# Sheet1_Cpu.net
KiCad netlist of a schematic drawn in Altium Designer
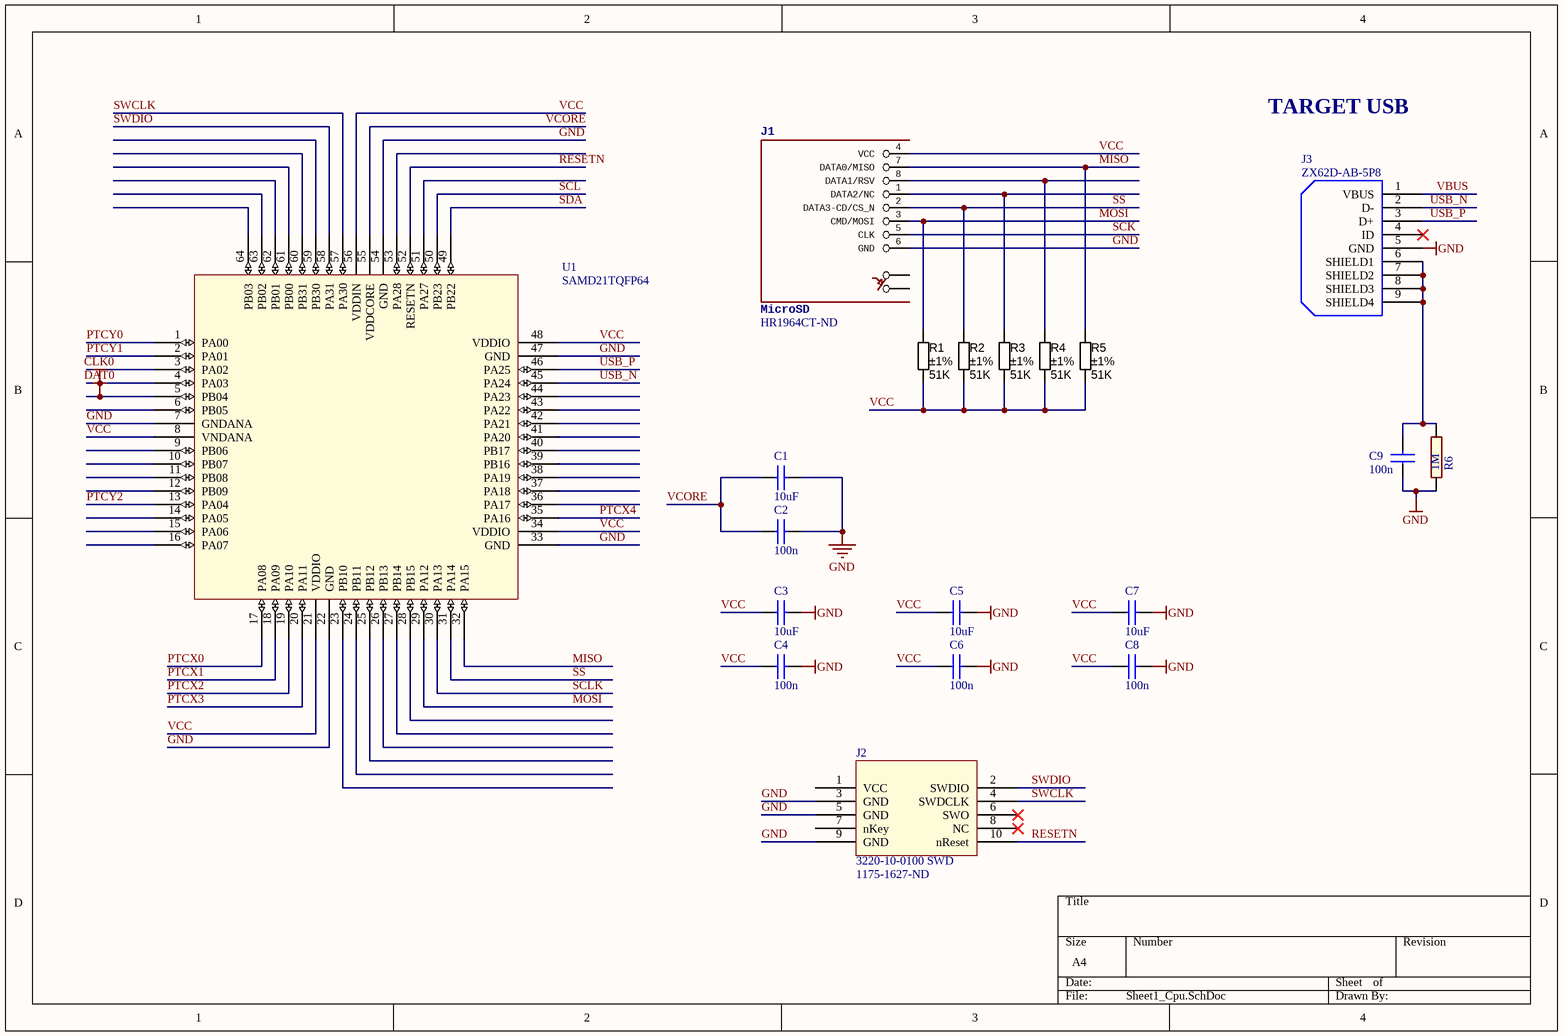
[diagram p0: Sheet1_Cpu.SchDoc]

(export (version "E")
  (design (tool "Eeschema 10.0.6"))
  (components
    (comp (ref "C1")
      (value "10uF")
      (footprint "AP1-00041")
      (description "Ceramic capacitor, SMD 0805, X5R, 10V, 10 %, (de19441)")
      (fields (field (name "TOLERANCE") "10%") (field (name "MANUFACTURER") "Murata"))
      (libsource (lib "AltiumDbLib") (part "CAP-NONPOL"))
    )
    (comp (ref "C2")
      (value "100n")
      (footprint "AP1-00001")
      (description "Ceramic capacitor, SMD 0402, X7R, 16V, +/-10%")
      (fields (field (name "TOLERANCE") "16V, +/-10%") (field (name "MANUFACTURER") "Kemet"))
      (libsource (lib "AltiumDbLib") (part "CAP-NONPOL"))
    )
    (comp (ref "C3")
      (value "10uF")
      (footprint "AP1-00041")
      (description "Ceramic capacitor, SMD 0805, X5R, 10V, 10 %, (de19441)")
      (fields (field (name "TOLERANCE") "10%") (field (name "MANUFACTURER") "Murata"))
      (libsource (lib "AltiumDbLib") (part "CAP-NONPOL"))
    )
    (comp (ref "C4")
      (value "100n")
      (footprint "AP1-00001")
      (description "Ceramic capacitor, SMD 0402, X7R, 16V, +/-10%")
      (fields (field (name "TOLERANCE") "16V, +/-10%") (field (name "MANUFACTURER") "Kemet"))
      (libsource (lib "AltiumDbLib") (part "CAP-NONPOL"))
    )
    (comp (ref "C5")
      (value "10uF")
      (footprint "AP1-00041")
      (description "Ceramic capacitor, SMD 0805, X5R, 10V, 10 %, (de19441)")
      (fields (field (name "TOLERANCE") "10%") (field (name "MANUFACTURER") "Murata"))
      (libsource (lib "AltiumDbLib") (part "CAP-NONPOL"))
    )
    (comp (ref "C6")
      (value "100n")
      (footprint "AP1-00001")
      (description "Ceramic capacitor, SMD 0402, X7R, 16V, +/-10%")
      (fields (field (name "TOLERANCE") "16V, +/-10%") (field (name "MANUFACTURER") "Kemet"))
      (libsource (lib "AltiumDbLib") (part "CAP-NONPOL"))
    )
    (comp (ref "C7")
      (value "10uF")
      (footprint "AP1-00041")
      (description "Ceramic capacitor, SMD 0805, X5R, 10V, 10 %, (de19441)")
      (fields (field (name "TOLERANCE") "10%") (field (name "MANUFACTURER") "Murata"))
      (libsource (lib "AltiumDbLib") (part "CAP-NONPOL"))
    )
    (comp (ref "C8")
      (value "100n")
      (footprint "AP1-00001")
      (description "Ceramic capacitor, SMD 0402, X7R, 16V, +/-10%")
      (fields (field (name "TOLERANCE") "16V, +/-10%") (field (name "MANUFACTURER") "Kemet"))
      (libsource (lib "AltiumDbLib") (part "CAP-NONPOL"))
    )
    (comp (ref "C9")
      (value "100n")
      (footprint "AP1-00001")
      (description "Ceramic capacitor, SMD 0402, X7R, 16V, +/-10%")
      (fields (field (name "TOLERANCE") "16V, +/-10%") (field (name "MANUFACTURER") "Kemet"))
      (libsource (lib "AltiumDbLib") (part "CAP-NONPOL"))
    )
    (comp (ref "J1")
      (value "MicroSD")
      (footprint "DM3AT-SF-PEJM5")
      (description "Hirose Electric Micro SD - DM3AT-SF-PEJM5")
      (fields (field (name "SUPPLIER PART NUMBER 1") "HR1964CT-ND"))
      (libsource (lib "DM3AT-SF-PEJM5") (part "DM3AT-SF-PEJM5"))
    )
    (comp (ref "J2")
      (value "3220-10-0100 SWD")
      (footprint "3220-10-0100")
      (description "HiRose 3220-10-0100 BOX HEADER, 0.050 10 POS")
      (fields (field (name "SUPPLIER PART NUMBER 1") "1175-1627-ND"))
      (libsource (lib "fastcar") (part "3220-10-0100-00"))
    )
    (comp (ref "J3")
      (value "ZX62D-AB-5P8")
      (footprint "AP8-00852")
      (description "Hirose ZX62D-AB-5P8 Micro USB AB Connector, Standard SMT + DIP")
      (libsource (lib "AltiumDbLib") (part "USB_AB"))
    )
    (comp (ref "R1")
      (value "51K")
      (footprint "RESC2012X70N")
      (description "Resistor SMD chip 51k Ohm 0.125W 1% 0805")
      (fields (field (name "TOLERANCE") "±1%") (field (name "Comment") "Thick Film"))
      (libsource (lib "") (part "RES_51K_0805_1%_1"))
    )
    (comp (ref "R2")
      (value "51K")
      (footprint "RESC2012X70N")
      (description "Resistor SMD chip 51k Ohm 0.125W 1% 0805")
      (fields (field (name "TOLERANCE") "±1%") (field (name "Comment") "Thick Film"))
      (libsource (lib "") (part "RES_51K_0805_1%_1"))
    )
    (comp (ref "R3")
      (value "51K")
      (footprint "RESC2012X70N")
      (description "Resistor SMD chip 51k Ohm 0.125W 1% 0805")
      (fields (field (name "TOLERANCE") "±1%") (field (name "Comment") "Thick Film"))
      (libsource (lib "PBL - Resistors") (part "RES_51K_0805_1%"))
    )
    (comp (ref "R4")
      (value "51K")
      (footprint "RESC2012X70N")
      (description "Resistor SMD chip 51k Ohm 0.125W 1% 0805")
      (fields (field (name "TOLERANCE") "±1%") (field (name "Comment") "Thick Film"))
      (libsource (lib "PBL - Resistors") (part "RES_51K_0805_1%"))
    )
    (comp (ref "R5")
      (value "51K")
      (footprint "RESC2012X70N")
      (description "Resistor SMD chip 51k Ohm 0.125W 1% 0805")
      (fields (field (name "TOLERANCE") "±1%") (field (name "Comment") "Thick Film"))
      (libsource (lib "PBL - Resistors") (part "RES_51K_0805_1%"))
    )
    (comp (ref "R6")
      (value "1M")
      (footprint "AP2-00011")
      (description "Thick film resistor, SMD 0402, 1/16W, 1%")
      (fields (field (name "TOLERANCE") "1 %") (field (name "MANUFACTURER") "KOA"))
      (libsource (lib "AltiumDbLib") (part "R2"))
    )
    (comp (ref "U1")
      (value "SAMD21TQFP64")
      (footprint "TSQFP50P1300X1300X120-64N")
      (libsource (lib "fastcar") (part "SAMD21TQFP64"))
    )
  )
  (nets
    (net (code "1") (name "/MISO") (class "Default")
      (node (ref "J1") (pin "7") (pinfunction "DATA0/MISO_7") (pintype "passive"))
      (node (ref "R5") (pin "1") (pinfunction "1_1") (pintype "passive"))
      (node (ref "U1") (pin "32") (pinfunction "PA15_32") (pintype "bidirectional"))
    )
    (net (code "2") (name "/MOSI") (class "Default")
      (node (ref "J1") (pin "3") (pinfunction "CMD/MOSI_3") (pintype "passive"))
      (node (ref "R1") (pin "2") (pinfunction "2_2") (pintype "passive"))
      (node (ref "U1") (pin "29") (pinfunction "PA12_29") (pintype "bidirectional"))
    )
    (net (code "3") (name "/PTCX0") (class "Default")
      (node (ref "U1") (pin "17") (pinfunction "PA08_17") (pintype "bidirectional"))
    )
    (net (code "4") (name "/PTCX1") (class "Default")
      (node (ref "U1") (pin "18") (pinfunction "PA09_18") (pintype "bidirectional"))
    )
    (net (code "5") (name "/PTCX2") (class "Default")
      (node (ref "U1") (pin "19") (pinfunction "PA10_19") (pintype "bidirectional"))
    )
    (net (code "6") (name "/PTCX3") (class "Default")
      (node (ref "U1") (pin "20") (pinfunction "PA11_20") (pintype "bidirectional"))
    )
    (net (code "7") (name "/PTCX4") (class "Default")
      (node (ref "U1") (pin "35") (pinfunction "PA16_35") (pintype "bidirectional"))
    )
    (net (code "8") (name "/PTCY0") (class "Default")
      (node (ref "U1") (pin "1") (pinfunction "PA00_1") (pintype "bidirectional"))
    )
    (net (code "9") (name "/PTCY1") (class "Default")
      (node (ref "U1") (pin "2") (pinfunction "PA01_2") (pintype "bidirectional"))
    )
    (net (code "10") (name "/PTCY2") (class "Default")
      (node (ref "U1") (pin "13") (pinfunction "PA04_13") (pintype "bidirectional"))
    )
    (net (code "11") (name "/RESETN") (class "Default")
      (node (ref "J2") (pin "10") (pinfunction "nReset_10") (pintype "passive"))
      (node (ref "U1") (pin "52") (pinfunction "RESETN_52") (pintype "bidirectional"))
    )
    (net (code "12") (name "/SCK") (class "Default")
      (node (ref "J1") (pin "5") (pinfunction "CLK_5") (pintype "passive"))
    )
    (net (code "13") (name "/SCL") (class "Default")
      (node (ref "U1") (pin "50") (pinfunction "PB23_50") (pintype "bidirectional"))
    )
    (net (code "14") (name "/SCLK") (class "Default")
      (node (ref "U1") (pin "30") (pinfunction "PA13_30") (pintype "bidirectional"))
    )
    (net (code "15") (name "/SDA") (class "Default")
      (node (ref "U1") (pin "49") (pinfunction "PB22_49") (pintype "bidirectional"))
    )
    (net (code "16") (name "/SS") (class "Default")
      (node (ref "J1") (pin "2") (pinfunction "DATA3-CD/CS_N_2") (pintype "passive"))
      (node (ref "R2") (pin "2") (pinfunction "2_2") (pintype "passive"))
      (node (ref "U1") (pin "31") (pinfunction "PA14_31") (pintype "bidirectional"))
    )
    (net (code "17") (name "/SWCLK") (class "Default")
      (node (ref "J2") (pin "4") (pinfunction "SWDCLK_4") (pintype "passive"))
      (node (ref "U1") (pin "57") (pinfunction "PA30_57") (pintype "bidirectional"))
    )
    (net (code "18") (name "/SWDIO") (class "Default")
      (node (ref "J2") (pin "2") (pinfunction "SWDIO_2") (pintype "passive"))
      (node (ref "U1") (pin "58") (pinfunction "PA31_58") (pintype "bidirectional"))
    )
    (net (code "19") (name "/USB_N") (class "Default")
      (node (ref "J3") (pin "2") (pinfunction "D-_2") (pintype "passive"))
      (node (ref "U1") (pin "45") (pinfunction "PA24_45") (pintype "bidirectional"))
    )
    (net (code "20") (name "/USB_P") (class "Default")
      (node (ref "J3") (pin "3") (pinfunction "D+_3") (pintype "passive"))
      (node (ref "U1") (pin "46") (pinfunction "PA25_46") (pintype "bidirectional"))
    )
    (net (code "21") (name "/VBUS") (class "Default")
      (node (ref "J3") (pin "1") (pinfunction "VBUS_1") (pintype "passive"))
    )
    (net (code "22") (name "/VCC") (class "Default")
      (node (ref "C3") (pin "1") (pinfunction "1_1") (pintype "passive"))
      (node (ref "C4") (pin "1") (pinfunction "1_1") (pintype "passive"))
      (node (ref "C5") (pin "1") (pinfunction "1_1") (pintype "passive"))
      (node (ref "C6") (pin "1") (pinfunction "1_1") (pintype "passive"))
      (node (ref "C7") (pin "1") (pinfunction "1_1") (pintype "passive"))
      (node (ref "C8") (pin "1") (pinfunction "1_1") (pintype "passive"))
      (node (ref "J1") (pin "4") (pinfunction "VCC_4") (pintype "passive"))
      (node (ref "R1") (pin "1") (pinfunction "1_1") (pintype "passive"))
      (node (ref "R2") (pin "1") (pinfunction "1_1") (pintype "passive"))
      (node (ref "R3") (pin "2") (pinfunction "2_2") (pintype "passive"))
      (node (ref "R4") (pin "2") (pinfunction "2_2") (pintype "passive"))
      (node (ref "R5") (pin "2") (pinfunction "2_2") (pintype "passive"))
      (node (ref "U1") (pin "21") (pinfunction "VDDIO_21") (pintype "power_in"))
      (node (ref "U1") (pin "34") (pinfunction "VDDIO_34") (pintype "power_in"))
      (node (ref "U1") (pin "48") (pinfunction "VDDIO_48") (pintype "power_in"))
      (node (ref "U1") (pin "56") (pinfunction "VDDIN_56") (pintype "power_in"))
      (node (ref "U1") (pin "8") (pinfunction "VNDANA_8") (pintype "power_in"))
    )
    (net (code "23") (name "/VCORE") (class "Default")
      (node (ref "C1") (pin "1") (pinfunction "1_1") (pintype "passive"))
      (node (ref "C2") (pin "1") (pinfunction "1_1") (pintype "passive"))
      (node (ref "U1") (pin "55") (pinfunction "VDDCORE_55") (pintype "power_in"))
    )
    (net (code "24") (name "CLK0") (class "Default")
      (node (ref "U1") (pin "4") (pinfunction "PA03_4") (pintype "bidirectional"))
    )
    (net (code "25") (name "DAT0") (class "Default")
      (node (ref "U1") (pin "5") (pinfunction "PB04_5") (pintype "bidirectional"))
    )
    (net (code "26") (name "GND") (class "Default")
      (node (ref "C1") (pin "2") (pinfunction "2_2") (pintype "passive"))
      (node (ref "C2") (pin "2") (pinfunction "2_2") (pintype "passive"))
      (node (ref "C3") (pin "2") (pinfunction "2_2") (pintype "passive"))
      (node (ref "C4") (pin "2") (pinfunction "2_2") (pintype "passive"))
      (node (ref "C5") (pin "2") (pinfunction "2_2") (pintype "passive"))
      (node (ref "C6") (pin "2") (pinfunction "2_2") (pintype "passive"))
      (node (ref "C7") (pin "2") (pinfunction "2_2") (pintype "passive"))
      (node (ref "C8") (pin "2") (pinfunction "2_2") (pintype "passive"))
      (node (ref "C9") (pin "1") (pinfunction "1_1") (pintype "passive"))
      (node (ref "J1") (pin "6") (pinfunction "GND_6") (pintype "passive"))
      (node (ref "J2") (pin "3") (pinfunction "GND_3") (pintype "passive"))
      (node (ref "J2") (pin "5") (pinfunction "GND_5") (pintype "passive"))
      (node (ref "J2") (pin "9") (pinfunction "GND_9") (pintype "passive"))
      (node (ref "J3") (pin "5") (pinfunction "GND_5") (pintype "passive"))
      (node (ref "R6") (pin "1") (pinfunction "1_1") (pintype "passive"))
      (node (ref "U1") (pin "22") (pinfunction "GND_22") (pintype "power_in"))
      (node (ref "U1") (pin "33") (pinfunction "GND_33") (pintype "power_in"))
      (node (ref "U1") (pin "47") (pinfunction "GND_47") (pintype "power_in"))
      (node (ref "U1") (pin "54") (pinfunction "GND_54") (pintype "power_in"))
      (node (ref "U1") (pin "7") (pinfunction "GNDANA_7") (pintype "power_in"))
    )
    (net (code "27") (name "Net-(J1-DATA1{slash}RSV)") (class "Default")
      (node (ref "J1") (pin "8") (pinfunction "DATA1/RSV_8") (pintype "passive"))
      (node (ref "R4") (pin "1") (pinfunction "1_1") (pintype "passive"))
    )
    (net (code "28") (name "Net-(J1-DATA2{slash}NC)") (class "Default")
      (node (ref "J1") (pin "1") (pinfunction "DATA2/NC_1") (pintype "passive"))
      (node (ref "R3") (pin "1") (pinfunction "1_1") (pintype "passive"))
    )
    (net (code "29") (name "Net-(J3-SHIELD1)") (class "Default")
      (node (ref "C9") (pin "2") (pinfunction "2_2") (pintype "passive"))
      (node (ref "J3") (pin "6") (pinfunction "SHIELD1_6") (pintype "passive"))
      (node (ref "J3") (pin "7") (pinfunction "SHIELD2_7") (pintype "passive"))
      (node (ref "J3") (pin "8") (pinfunction "SHIELD3_8") (pintype "passive"))
      (node (ref "J3") (pin "9") (pinfunction "SHIELD4_9") (pintype "passive"))
      (node (ref "R6") (pin "2") (pinfunction "2_2") (pintype "passive"))
    )
    (net (code "30") (name "unconnected-(J1-PadA)") (class "Default")
      (node (ref "J1") (pin "A") (pinfunction "A_A") (pintype "passive"))
    )
    (net (code "31") (name "unconnected-(J1-PadB)") (class "Default")
      (node (ref "J1") (pin "B") (pinfunction "B_B") (pintype "passive"))
    )
    (net (code "32") (name "unconnected-(J2-NC-Pad8)") (class "Default")
      (node (ref "J2") (pin "8") (pinfunction "NC_8") (pintype "passive+no_connect"))
    )
    (net (code "33") (name "unconnected-(J2-SWO-Pad6)") (class "Default")
      (node (ref "J2") (pin "6") (pinfunction "SWO_6") (pintype "passive+no_connect"))
    )
    (net (code "34") (name "unconnected-(J2-VCC-Pad1)") (class "Default")
      (node (ref "J2") (pin "1") (pinfunction "VCC_1") (pintype "passive"))
    )
    (net (code "35") (name "unconnected-(J2-nKey-Pad7)") (class "Default")
      (node (ref "J2") (pin "7") (pinfunction "nKey_7") (pintype "passive"))
    )
    (net (code "36") (name "unconnected-(J3-ID-Pad4)") (class "Default")
      (node (ref "J3") (pin "4") (pinfunction "ID_4") (pintype "passive+no_connect"))
    )
    (net (code "37") (name "unconnected-(U1-PA02-Pad3)") (class "Default")
      (node (ref "U1") (pin "3") (pinfunction "PA02_3") (pintype "bidirectional"))
    )
    (net (code "38") (name "unconnected-(U1-PA05-Pad14)") (class "Default")
      (node (ref "U1") (pin "14") (pinfunction "PA05_14") (pintype "bidirectional"))
    )
    (net (code "39") (name "unconnected-(U1-PA06-Pad15)") (class "Default")
      (node (ref "U1") (pin "15") (pinfunction "PA06_15") (pintype "bidirectional"))
    )
    (net (code "40") (name "unconnected-(U1-PA07-Pad16)") (class "Default")
      (node (ref "U1") (pin "16") (pinfunction "PA07_16") (pintype "bidirectional"))
    )
    (net (code "41") (name "unconnected-(U1-PA17-Pad36)") (class "Default")
      (node (ref "U1") (pin "36") (pinfunction "PA17_36") (pintype "bidirectional"))
    )
    (net (code "42") (name "unconnected-(U1-PA18-Pad37)") (class "Default")
      (node (ref "U1") (pin "37") (pinfunction "PA18_37") (pintype "bidirectional"))
    )
    (net (code "43") (name "unconnected-(U1-PA19-Pad38)") (class "Default")
      (node (ref "U1") (pin "38") (pinfunction "PA19_38") (pintype "bidirectional"))
    )
    (net (code "44") (name "unconnected-(U1-PA20-Pad41)") (class "Default")
      (node (ref "U1") (pin "41") (pinfunction "PA20_41") (pintype "bidirectional"))
    )
    (net (code "45") (name "unconnected-(U1-PA21-Pad42)") (class "Default")
      (node (ref "U1") (pin "42") (pinfunction "PA21_42") (pintype "bidirectional"))
    )
    (net (code "46") (name "unconnected-(U1-PA22-Pad43)") (class "Default")
      (node (ref "U1") (pin "43") (pinfunction "PA22_43") (pintype "bidirectional"))
    )
    (net (code "47") (name "unconnected-(U1-PA23-Pad44)") (class "Default")
      (node (ref "U1") (pin "44") (pinfunction "PA23_44") (pintype "bidirectional"))
    )
    (net (code "48") (name "unconnected-(U1-PA27-Pad51)") (class "Default")
      (node (ref "U1") (pin "51") (pinfunction "PA27_51") (pintype "bidirectional"))
    )
    (net (code "49") (name "unconnected-(U1-PA28-Pad53)") (class "Default")
      (node (ref "U1") (pin "53") (pinfunction "PA28_53") (pintype "bidirectional"))
    )
    (net (code "50") (name "unconnected-(U1-PB00-Pad61)") (class "Default")
      (node (ref "U1") (pin "61") (pinfunction "PB00_61") (pintype "bidirectional"))
    )
    (net (code "51") (name "unconnected-(U1-PB01-Pad62)") (class "Default")
      (node (ref "U1") (pin "62") (pinfunction "PB01_62") (pintype "bidirectional"))
    )
    (net (code "52") (name "unconnected-(U1-PB02-Pad63)") (class "Default")
      (node (ref "U1") (pin "63") (pinfunction "PB02_63") (pintype "bidirectional"))
    )
    (net (code "53") (name "unconnected-(U1-PB03-Pad64)") (class "Default")
      (node (ref "U1") (pin "64") (pinfunction "PB03_64") (pintype "bidirectional"))
    )
    (net (code "54") (name "unconnected-(U1-PB05-Pad6)") (class "Default")
      (node (ref "U1") (pin "6") (pinfunction "PB05_6") (pintype "bidirectional"))
    )
    (net (code "55") (name "unconnected-(U1-PB06-Pad9)") (class "Default")
      (node (ref "U1") (pin "9") (pinfunction "PB06_9") (pintype "bidirectional"))
    )
    (net (code "56") (name "unconnected-(U1-PB07-Pad10)") (class "Default")
      (node (ref "U1") (pin "10") (pinfunction "PB07_10") (pintype "bidirectional"))
    )
    (net (code "57") (name "unconnected-(U1-PB08-Pad11)") (class "Default")
      (node (ref "U1") (pin "11") (pinfunction "PB08_11") (pintype "bidirectional"))
    )
    (net (code "58") (name "unconnected-(U1-PB09-Pad12)") (class "Default")
      (node (ref "U1") (pin "12") (pinfunction "PB09_12") (pintype "bidirectional"))
    )
    (net (code "59") (name "unconnected-(U1-PB10-Pad23)") (class "Default")
      (node (ref "U1") (pin "23") (pinfunction "PB10_23") (pintype "bidirectional"))
    )
    (net (code "60") (name "unconnected-(U1-PB11-Pad24)") (class "Default")
      (node (ref "U1") (pin "24") (pinfunction "PB11_24") (pintype "bidirectional"))
    )
    (net (code "61") (name "unconnected-(U1-PB12-Pad25)") (class "Default")
      (node (ref "U1") (pin "25") (pinfunction "PB12_25") (pintype "bidirectional"))
    )
    (net (code "62") (name "unconnected-(U1-PB13-Pad26)") (class "Default")
      (node (ref "U1") (pin "26") (pinfunction "PB13_26") (pintype "bidirectional"))
    )
    (net (code "63") (name "unconnected-(U1-PB14-Pad27)") (class "Default")
      (node (ref "U1") (pin "27") (pinfunction "PB14_27") (pintype "bidirectional"))
    )
    (net (code "64") (name "unconnected-(U1-PB15-Pad28)") (class "Default")
      (node (ref "U1") (pin "28") (pinfunction "PB15_28") (pintype "bidirectional"))
    )
    (net (code "65") (name "unconnected-(U1-PB16-Pad39)") (class "Default")
      (node (ref "U1") (pin "39") (pinfunction "PB16_39") (pintype "bidirectional"))
    )
    (net (code "66") (name "unconnected-(U1-PB17-Pad40)") (class "Default")
      (node (ref "U1") (pin "40") (pinfunction "PB17_40") (pintype "bidirectional"))
    )
    (net (code "67") (name "unconnected-(U1-PB30-Pad59)") (class "Default")
      (node (ref "U1") (pin "59") (pinfunction "PB30_59") (pintype "bidirectional"))
    )
    (net (code "68") (name "unconnected-(U1-PB31-Pad60)") (class "Default")
      (node (ref "U1") (pin "60") (pinfunction "PB31_60") (pintype "bidirectional"))
    )
  )
)
